# RX-Super-Regenerative-Aurel-ASR2.net
KiCad netlist of a schematic drawn in EAGLE
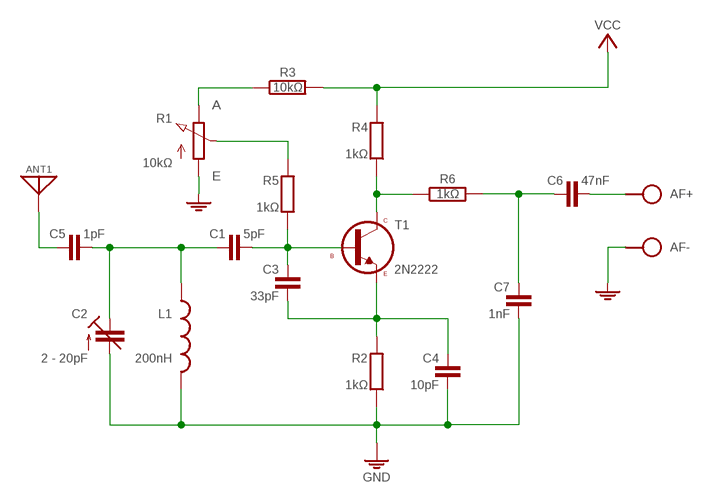
[diagram p0: schematic, sheet 1]

(export (version "E")
  (design (tool "Eeschema 10.0.6"))
  (components
    (comp (ref "AF")
      (value "SPAD+-+-")
      (footprint "eagle-import:SPAD+-")
      (libsource (lib "eagle-import") (part "SPAD+-+-"))
    )
    (comp (ref "ANT1")
      (value "ANT")
      (footprint "eagle-import:SPAD")
      (libsource (lib "eagle-import") (part "ANT"))
    )
    (comp (ref "C1")
      (value "5pF")
      (footprint "eagle-import:C025-015X024")
      (libsource (lib "eagle-import") (part "C-H025-015X024"))
    )
    (comp (ref "C2")
      (value "2 - 20pF")
      (footprint "eagle-import:TRIM-2222-808")
      (libsource (lib "eagle-import") (part "C-TR-PH201272222-808-2PINB"))
    )
    (comp (ref "C3")
      (value "33pF")
      (footprint "eagle-import:C025-015X024")
      (libsource (lib "eagle-import") (part "C025-015X024"))
    )
    (comp (ref "C4")
      (value "10pF")
      (footprint "eagle-import:C025-015X024")
      (libsource (lib "eagle-import") (part "C025-015X024"))
    )
    (comp (ref "C5")
      (value "1pF")
      (footprint "eagle-import:C025-015X024")
      (libsource (lib "eagle-import") (part "C-H025-015X024"))
    )
    (comp (ref "C6")
      (value "47nF")
      (footprint "eagle-import:C050-020X044")
      (libsource (lib "eagle-import") (part "C-H050-020X044"))
    )
    (comp (ref "C7")
      (value "1nF")
      (footprint "eagle-import:C050-020X044_V")
      (libsource (lib "eagle-import") (part "C050-020X044/V"))
    )
    (comp (ref "L1")
      (value "200nH")
      (footprint "eagle-import:L-04_7-V")
      (libsource (lib "eagle-import") (part "L04/7-V"))
    )
    (comp (ref "R1")
      (value "10kΩ")
      (footprint "eagle-import:POT")
      (libsource (lib "eagle-import") (part "POT"))
    )
    (comp (ref "R2")
      (value "1kΩ")
      (footprint "eagle-import:0204_10-V")
      (libsource (lib "eagle-import") (part "R0204/10-V"))
    )
    (comp (ref "R3")
      (value "10kΩ")
      (footprint "eagle-import:0204_10")
      (libsource (lib "eagle-import") (part "R-H0204/10"))
    )
    (comp (ref "R4")
      (value "1kΩ")
      (footprint "eagle-import:0204_10-V")
      (libsource (lib "eagle-import") (part "R0204/10-V"))
    )
    (comp (ref "R5")
      (value "1kΩ")
      (footprint "eagle-import:0204_10-V")
      (libsource (lib "eagle-import") (part "R0204/10-V"))
    )
    (comp (ref "R6")
      (value "1kΩ")
      (footprint "eagle-import:0204_10")
      (libsource (lib "eagle-import") (part "R-H0204/10"))
    )
    (comp (ref "S2")
      (value "VCC_GNDPWR-L")
      (footprint "eagle-import:PWR-L")
      (libsource (lib "eagle-import") (part "VCC_GNDPWR-L"))
    )
    (comp (ref "T1")
      (value "2N2222")
      (footprint "eagle-import:TO92-EBC")
      (libsource (lib "eagle-import") (part "2N2222"))
    )
  )
  (nets
    (net (code "1") (name "GND") (class "Default")
      (node (ref "AF") (pin "1") (pinfunction "P$1_1") (pintype "passive"))
      (node (ref "C2") (pin "2") (pinfunction "A_2") (pintype "passive"))
      (node (ref "C4") (pin "2") (pinfunction "2_2") (pintype "passive"))
      (node (ref "C7") (pin "2") (pinfunction "2_2") (pintype "passive"))
      (node (ref "L1") (pin "2") (pinfunction "2_2") (pintype "passive"))
      (node (ref "R1") (pin "A") (pinfunction "A_A") (pintype "passive"))
      (node (ref "R2") (pin "2") (pinfunction "1_2") (pintype "passive"))
      (node (ref "S2") (pin "1") (pinfunction "GND_1") (pintype "power_in"))
    )
    (net (code "2") (name "Net-(AFA-P$1)") (class "Default")
      (node (ref "AF") (pin "2") (pinfunction "P$1_2") (pintype "passive"))
      (node (ref "C6") (pin "2") (pinfunction "2_2") (pintype "passive"))
    )
    (net (code "3") (name "Net-(ANT1-Pad1)") (class "Default")
      (node (ref "ANT1") (pin "1") (pinfunction "1_1") (pintype "output"))
      (node (ref "C5") (pin "1") (pinfunction "1_1") (pintype "passive"))
    )
    (net (code "4") (name "Net-(C2-E)") (class "Default")
      (node (ref "C1") (pin "1") (pinfunction "1_1") (pintype "passive"))
      (node (ref "C2") (pin "3") (pinfunction "E_3") (pintype "passive"))
      (node (ref "C5") (pin "2") (pinfunction "2_2") (pintype "passive"))
      (node (ref "L1") (pin "1") (pinfunction "1_1") (pintype "passive"))
    )
    (net (code "5") (name "Net-(C6-Pad1)") (class "Default")
      (node (ref "C6") (pin "1") (pinfunction "1_1") (pintype "passive"))
      (node (ref "C7") (pin "1") (pinfunction "1_1") (pintype "passive"))
      (node (ref "R6") (pin "2") (pinfunction "2_2") (pintype "passive"))
    )
    (net (code "6") (name "Net-(R1-PadE)") (class "Default")
      (node (ref "R1") (pin "E") (pinfunction "E_E") (pintype "passive"))
      (node (ref "R3") (pin "1") (pinfunction "1_1") (pintype "passive"))
    )
    (net (code "7") (name "Net-(R2-2)") (class "Default")
      (node (ref "C3") (pin "2") (pinfunction "2_2") (pintype "passive"))
      (node (ref "C4") (pin "1") (pinfunction "1_1") (pintype "passive"))
      (node (ref "R2") (pin "1") (pinfunction "2_1") (pintype "passive"))
      (node (ref "T1") (pin "E") (pinfunction "E_E") (pintype "passive"))
    )
    (net (code "8") (name "Net-(R4-1)") (class "Default")
      (node (ref "R4") (pin "2") (pinfunction "1_2") (pintype "passive"))
      (node (ref "R6") (pin "1") (pinfunction "1_1") (pintype "passive"))
      (node (ref "T1") (pin "C") (pinfunction "C_C") (pintype "passive"))
    )
    (net (code "9") (name "Net-(R4-2)") (class "Default")
      (node (ref "R3") (pin "2") (pinfunction "2_2") (pintype "passive"))
      (node (ref "R4") (pin "1") (pinfunction "2_1") (pintype "passive"))
      (node (ref "S2") (pin "2") (pinfunction "VCC_2") (pintype "power_in"))
    )
    (net (code "10") (name "Net-(R5-1)") (class "Default")
      (node (ref "C1") (pin "2") (pinfunction "2_2") (pintype "passive"))
      (node (ref "C3") (pin "1") (pinfunction "1_1") (pintype "passive"))
      (node (ref "R5") (pin "2") (pinfunction "1_2") (pintype "passive"))
      (node (ref "T1") (pin "B") (pinfunction "B_B") (pintype "passive"))
    )
    (net (code "11") (name "Net-(R5-2)") (class "Default")
      (node (ref "R1") (pin "S") (pinfunction "S_S") (pintype "passive"))
      (node (ref "R5") (pin "1") (pinfunction "2_1") (pintype "passive"))
    )
  )
)
